# FLT04A.net
KiCad netlist of a schematic drawn in EAGLE
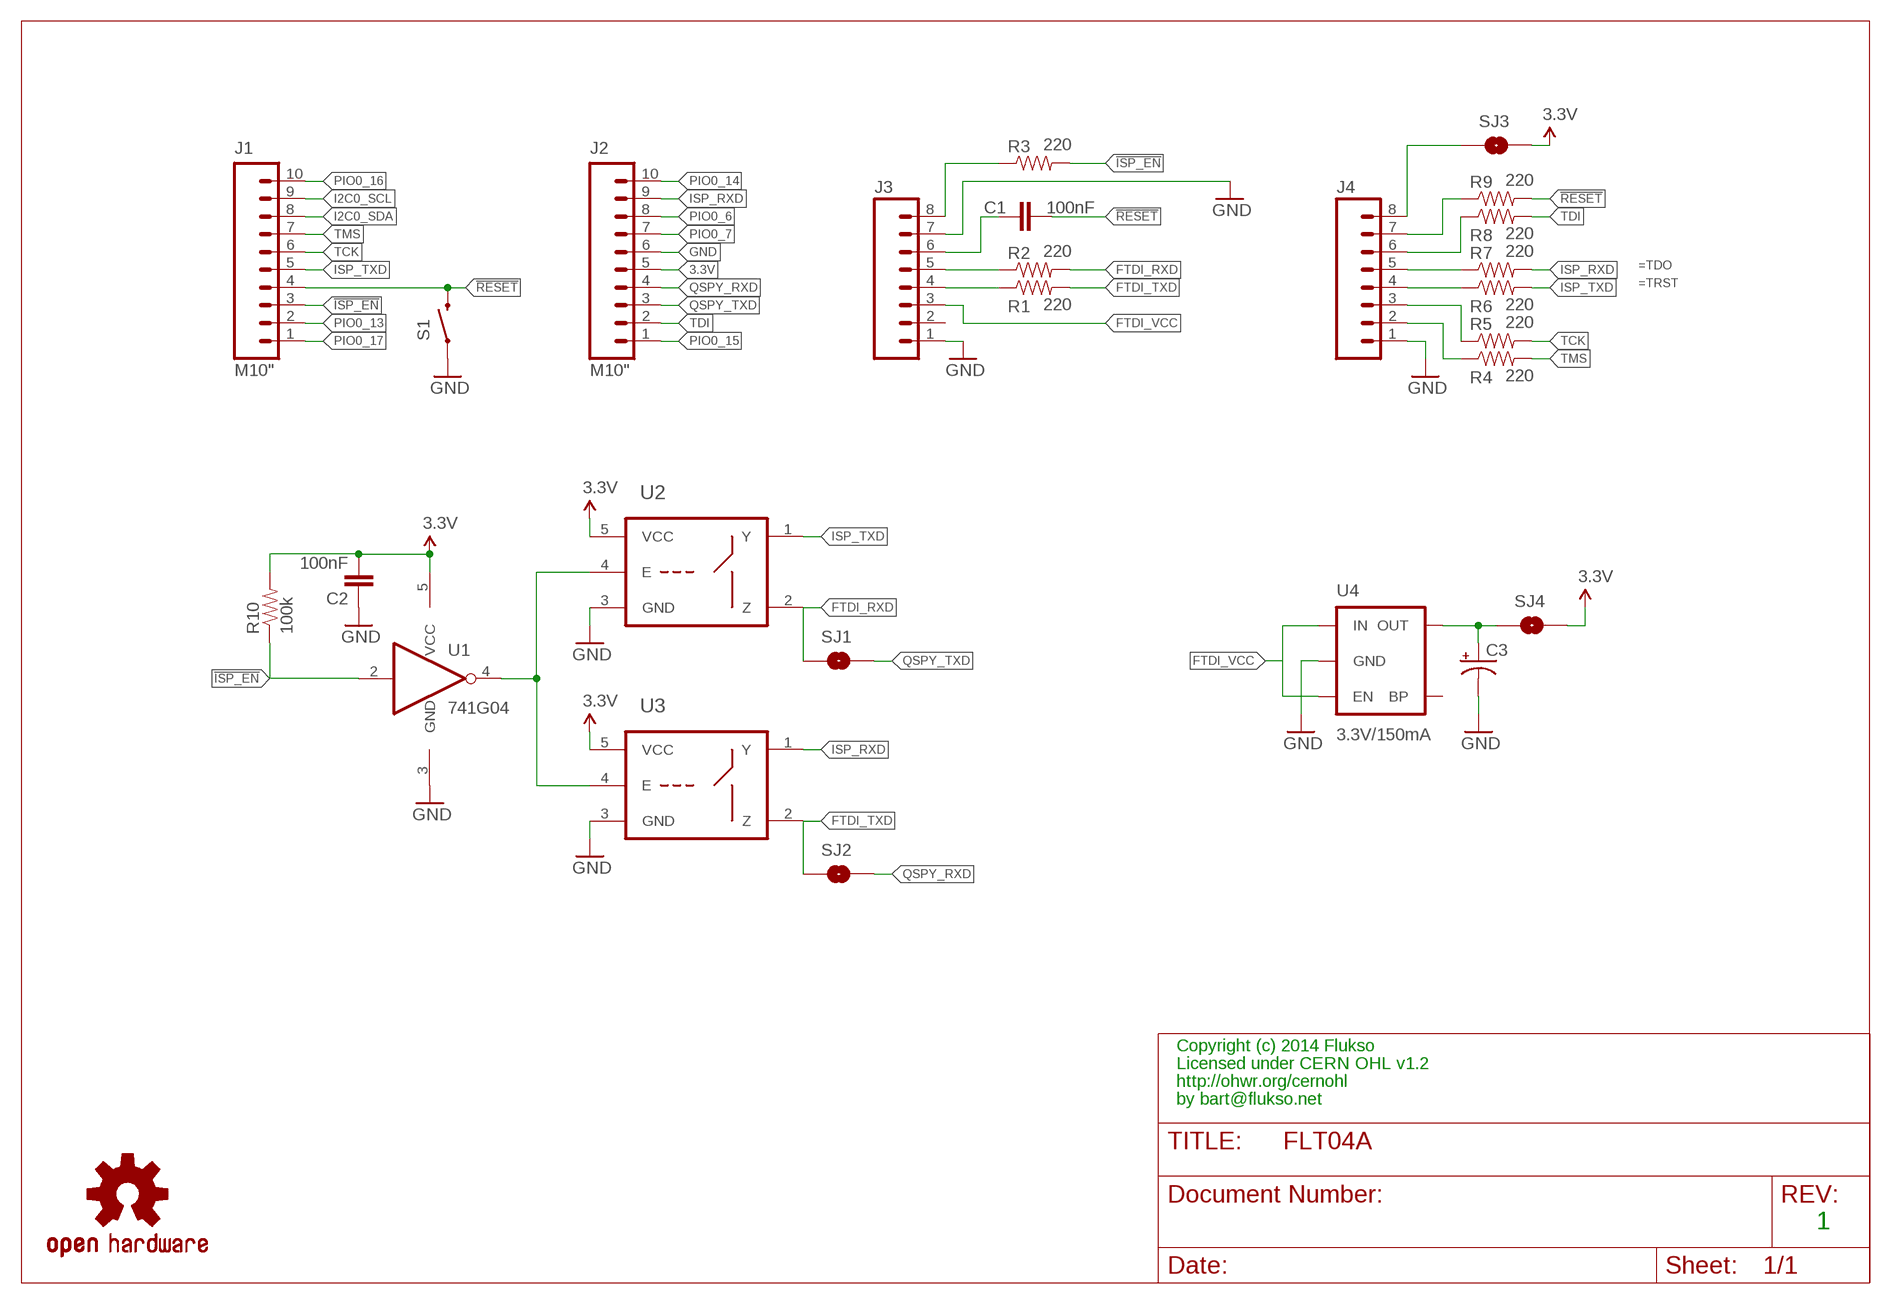
[diagram p0: schematic, sheet 1]

(export (version "E")
  (design (tool "Eeschema 10.0.6"))
  (components
    (comp (ref "C1")
      (value "100nF")
      (footprint "eagle-import:0402-CAP")
      (libsource (lib "eagle-import") (part "CAP0402-CAP"))
    )
    (comp (ref "C2")
      (value "100nF")
      (footprint "eagle-import:0402-CAP")
      (libsource (lib "eagle-import") (part "CAP0402-CAP"))
    )
    (comp (ref "C3")
      (value "CAP_POL1206")
      (footprint "eagle-import:EIA3216")
      (libsource (lib "eagle-import") (part "CAP_POL1206"))
    )
    (comp (ref "J1")
      (value "M10\"")
      (footprint "eagle-import:1X10")
      (libsource (lib "eagle-import") (part "M10{dblquote}"))
    )
    (comp (ref "J2")
      (value "M10\"")
      (footprint "eagle-import:1X10")
      (libsource (lib "eagle-import") (part "M10{dblquote}"))
    )
    (comp (ref "J3")
      (value "M08")
      (footprint "eagle-import:1X08_PIN1_NO_SILK")
      (libsource (lib "eagle-import") (part "M08"))
    )
    (comp (ref "J4")
      (value "M08")
      (footprint "eagle-import:1X08_PIN1_NO_SILK")
      (libsource (lib "eagle-import") (part "M08"))
    )
    (comp (ref "R1")
      (value "220")
      (footprint "eagle-import:0402-RES")
      (libsource (lib "eagle-import") (part "RESISTOR0402-RES"))
    )
    (comp (ref "R2")
      (value "220")
      (footprint "eagle-import:0402-RES")
      (libsource (lib "eagle-import") (part "RESISTOR0402-RES"))
    )
    (comp (ref "R3")
      (value "220")
      (footprint "eagle-import:0402-RES")
      (libsource (lib "eagle-import") (part "RESISTOR0402-RES"))
    )
    (comp (ref "R4")
      (value "220")
      (footprint "eagle-import:0402-RES")
      (libsource (lib "eagle-import") (part "RESISTOR0402-RES"))
    )
    (comp (ref "R5")
      (value "220")
      (footprint "eagle-import:0402-RES")
      (libsource (lib "eagle-import") (part "RESISTOR0402-RES"))
    )
    (comp (ref "R6")
      (value "220")
      (footprint "eagle-import:0402-RES")
      (libsource (lib "eagle-import") (part "RESISTOR0402-RES"))
    )
    (comp (ref "R7")
      (value "220")
      (footprint "eagle-import:0402-RES")
      (libsource (lib "eagle-import") (part "RESISTOR0402-RES"))
    )
    (comp (ref "R8")
      (value "220")
      (footprint "eagle-import:0402-RES")
      (libsource (lib "eagle-import") (part "RESISTOR0402-RES"))
    )
    (comp (ref "R9")
      (value "220")
      (footprint "eagle-import:0402-RES")
      (libsource (lib "eagle-import") (part "RESISTOR0402-RES"))
    )
    (comp (ref "R10")
      (value "100k")
      (footprint "eagle-import:0402-RES")
      (libsource (lib "eagle-import") (part "RESISTOR0402-RES"))
    )
    (comp (ref "S1")
      (value "SWITCH-MOMENTARY-2SMD")
      (footprint "eagle-import:TACTILE_SWITCH_SMD")
      (libsource (lib "eagle-import") (part "SWITCH-MOMENTARY-2SMD"))
    )
    (comp (ref "SJ1")
      (value "SOLDERJUMPERNC")
      (footprint "eagle-import:SJ_2S")
      (libsource (lib "eagle-import") (part "SOLDERJUMPERNC"))
    )
    (comp (ref "SJ2")
      (value "SOLDERJUMPERNC")
      (footprint "eagle-import:SJ_2S")
      (libsource (lib "eagle-import") (part "SOLDERJUMPERNC"))
    )
    (comp (ref "SJ3")
      (value "SOLDERJUMPERNC")
      (footprint "eagle-import:SJ_2S")
      (libsource (lib "eagle-import") (part "SOLDERJUMPERNC"))
    )
    (comp (ref "SJ4")
      (value "SOLDERJUMPERNC")
      (footprint "eagle-import:SJ_2S")
      (libsource (lib "eagle-import") (part "SOLDERJUMPERNC"))
    )
    (comp (ref "U$1")
      (value "OSHW-LOGOS")
      (footprint "eagle-import:OSHW-LOGO-S")
      (libsource (lib "eagle-import") (part "OSHW-LOGOS"))
    )
    (comp (ref "U1")
      (value "741G04")
      (footprint "eagle-import:SOT353")
      (libsource (lib "eagle-import") (part "741G04"))
    )
    (comp (ref "U2")
      (value "741G66")
      (footprint "eagle-import:SOT353")
      (libsource (lib "eagle-import") (part "741G66"))
    )
    (comp (ref "U3")
      (value "741G66")
      (footprint "eagle-import:SOT353")
      (libsource (lib "eagle-import") (part "741G66"))
    )
    (comp (ref "U4")
      (value "3.3V/150mA")
      (footprint "eagle-import:SOT23-5")
      (libsource (lib "eagle-import") (part "V_REG_MIC52053.3V"))
    )
  )
  (nets
    (net (code "1") (name "/~{ISP_EN}") (class "Default")
      (node (ref "J1") (pin "3") (pinfunction "3_3") (pintype "passive"))
      (node (ref "R10") (pin "1") (pinfunction "1_1") (pintype "passive"))
      (node (ref "R3") (pin "2") (pinfunction "2_2") (pintype "passive"))
      (node (ref "U1") (pin "2") (pinfunction "I_2") (pintype "input"))
    )
    (net (code "2") (name "/~{RESET}") (class "Default")
      (node (ref "C1") (pin "2") (pinfunction "2_2") (pintype "passive"))
      (node (ref "J1") (pin "4") (pinfunction "4_4") (pintype "passive"))
      (node (ref "R9") (pin "2") (pinfunction "2_2") (pintype "passive"))
      (node (ref "S1") (pin "3") (pinfunction "2_3") (pintype "passive"))
    )
    (net (code "3") (name "3.3V") (class "Default")
      (node (ref "C2") (pin "2") (pinfunction "2_2") (pintype "passive"))
      (node (ref "J2") (pin "5") (pinfunction "5_5") (pintype "passive"))
      (node (ref "R10") (pin "2") (pinfunction "2_2") (pintype "passive"))
      (node (ref "SJ3") (pin "2") (pinfunction "2_2") (pintype "passive"))
      (node (ref "SJ4") (pin "2") (pinfunction "2_2") (pintype "passive"))
      (node (ref "U1") (pin "5") (pinfunction "VCC_5") (pintype "power_in"))
      (node (ref "U2") (pin "5") (pinfunction "VCC_5") (pintype "power_in"))
      (node (ref "U3") (pin "5") (pinfunction "VCC_5") (pintype "power_in"))
    )
    (net (code "4") (name "FTDI_RXD") (class "Default")
      (node (ref "R2") (pin "2") (pinfunction "2_2") (pintype "passive"))
      (node (ref "SJ1") (pin "1") (pinfunction "1_1") (pintype "passive"))
      (node (ref "U2") (pin "2") (pinfunction "Z_2") (pintype "bidirectional"))
    )
    (net (code "5") (name "FTDI_TXD") (class "Default")
      (node (ref "R1") (pin "2") (pinfunction "2_2") (pintype "passive"))
      (node (ref "SJ2") (pin "1") (pinfunction "1_1") (pintype "passive"))
      (node (ref "U3") (pin "2") (pinfunction "Z_2") (pintype "bidirectional"))
    )
    (net (code "6") (name "FTDI_VCC") (class "Default")
      (node (ref "J3") (pin "3") (pinfunction "3_3") (pintype "passive"))
      (node (ref "U4") (pin "1") (pinfunction "IN_1") (pintype "input"))
      (node (ref "U4") (pin "3") (pinfunction "EN_3") (pintype "input"))
    )
    (net (code "7") (name "GND") (class "Default")
      (node (ref "C2") (pin "1") (pinfunction "1_1") (pintype "passive"))
      (node (ref "C3") (pin "C") (pinfunction "-_C") (pintype "passive"))
      (node (ref "J2") (pin "6") (pinfunction "6_6") (pintype "passive"))
      (node (ref "J3") (pin "1") (pinfunction "1_1") (pintype "passive"))
      (node (ref "J3") (pin "7") (pinfunction "7_7") (pintype "passive"))
      (node (ref "J4") (pin "1") (pinfunction "1_1") (pintype "passive"))
      (node (ref "S1") (pin "1") (pinfunction "1_1") (pintype "passive"))
      (node (ref "U1") (pin "3") (pinfunction "GND_3") (pintype "passive"))
      (node (ref "U2") (pin "3") (pinfunction "GND_3") (pintype "passive"))
      (node (ref "U3") (pin "3") (pinfunction "GND_3") (pintype "passive"))
      (node (ref "U4") (pin "2") (pinfunction "GND_2") (pintype "input"))
    )
    (net (code "8") (name "I2C0_SCL") (class "Default")
      (node (ref "J1") (pin "9") (pinfunction "9_9") (pintype "passive"))
    )
    (net (code "9") (name "I2C0_SDA") (class "Default")
      (node (ref "J1") (pin "8") (pinfunction "8_8") (pintype "passive"))
    )
    (net (code "10") (name "ISP_RXD") (class "Default")
      (node (ref "J2") (pin "9") (pinfunction "9_9") (pintype "passive"))
      (node (ref "R7") (pin "2") (pinfunction "2_2") (pintype "passive"))
      (node (ref "U3") (pin "1") (pinfunction "Y_1") (pintype "bidirectional"))
    )
    (net (code "11") (name "ISP_TXD") (class "Default")
      (node (ref "J1") (pin "5") (pinfunction "5_5") (pintype "passive"))
      (node (ref "R6") (pin "2") (pinfunction "2_2") (pintype "passive"))
      (node (ref "U2") (pin "1") (pinfunction "Y_1") (pintype "bidirectional"))
    )
    (net (code "12") (name "Net-(C1-Pad1)") (class "Default")
      (node (ref "C1") (pin "1") (pinfunction "1_1") (pintype "passive"))
      (node (ref "J3") (pin "6") (pinfunction "6_6") (pintype "passive"))
    )
    (net (code "13") (name "Net-(C3-+)") (class "Default")
      (node (ref "C3") (pin "A") (pinfunction "+_A") (pintype "passive"))
      (node (ref "SJ4") (pin "1") (pinfunction "1_1") (pintype "passive"))
      (node (ref "U4") (pin "5") (pinfunction "OUT_5") (pintype "passive"))
    )
    (net (code "14") (name "Net-(J3-Pad4)") (class "Default")
      (node (ref "J3") (pin "4") (pinfunction "4_4") (pintype "passive"))
      (node (ref "R1") (pin "1") (pinfunction "1_1") (pintype "passive"))
    )
    (net (code "15") (name "Net-(J3-Pad5)") (class "Default")
      (node (ref "J3") (pin "5") (pinfunction "5_5") (pintype "passive"))
      (node (ref "R2") (pin "1") (pinfunction "1_1") (pintype "passive"))
    )
    (net (code "16") (name "Net-(J3-Pad8)") (class "Default")
      (node (ref "J3") (pin "8") (pinfunction "8_8") (pintype "passive"))
      (node (ref "R3") (pin "1") (pinfunction "1_1") (pintype "passive"))
    )
    (net (code "17") (name "Net-(J4-Pad2)") (class "Default")
      (node (ref "J4") (pin "2") (pinfunction "2_2") (pintype "passive"))
      (node (ref "R4") (pin "1") (pinfunction "1_1") (pintype "passive"))
    )
    (net (code "18") (name "Net-(J4-Pad3)") (class "Default")
      (node (ref "J4") (pin "3") (pinfunction "3_3") (pintype "passive"))
      (node (ref "R5") (pin "1") (pinfunction "1_1") (pintype "passive"))
    )
    (net (code "19") (name "Net-(J4-Pad4)") (class "Default")
      (node (ref "J4") (pin "4") (pinfunction "4_4") (pintype "passive"))
      (node (ref "R6") (pin "1") (pinfunction "1_1") (pintype "passive"))
    )
    (net (code "20") (name "Net-(J4-Pad5)") (class "Default")
      (node (ref "J4") (pin "5") (pinfunction "5_5") (pintype "passive"))
      (node (ref "R7") (pin "1") (pinfunction "1_1") (pintype "passive"))
    )
    (net (code "21") (name "Net-(J4-Pad6)") (class "Default")
      (node (ref "J4") (pin "6") (pinfunction "6_6") (pintype "passive"))
      (node (ref "R8") (pin "1") (pinfunction "1_1") (pintype "passive"))
    )
    (net (code "22") (name "Net-(J4-Pad7)") (class "Default")
      (node (ref "J4") (pin "7") (pinfunction "7_7") (pintype "passive"))
      (node (ref "R9") (pin "1") (pinfunction "1_1") (pintype "passive"))
    )
    (net (code "23") (name "Net-(J4-Pad8)") (class "Default")
      (node (ref "J4") (pin "8") (pinfunction "8_8") (pintype "passive"))
      (node (ref "SJ3") (pin "1") (pinfunction "1_1") (pintype "passive"))
    )
    (net (code "24") (name "Net-(U1-O)") (class "Default")
      (node (ref "U1") (pin "4") (pinfunction "O_4") (pintype "output"))
      (node (ref "U2") (pin "4") (pinfunction "E_4") (pintype "input"))
      (node (ref "U3") (pin "4") (pinfunction "E_4") (pintype "input"))
    )
    (net (code "25") (name "PIO0_6") (class "Default")
      (node (ref "J2") (pin "8") (pinfunction "8_8") (pintype "passive"))
    )
    (net (code "26") (name "PIO0_7") (class "Default")
      (node (ref "J2") (pin "7") (pinfunction "7_7") (pintype "passive"))
    )
    (net (code "27") (name "PIO0_13") (class "Default")
      (node (ref "J1") (pin "2") (pinfunction "2_2") (pintype "passive"))
    )
    (net (code "28") (name "PIO0_14") (class "Default")
      (node (ref "J2") (pin "10") (pinfunction "10_10") (pintype "passive"))
    )
    (net (code "29") (name "PIO0_15") (class "Default")
      (node (ref "J2") (pin "1") (pinfunction "1_1") (pintype "passive"))
    )
    (net (code "30") (name "PIO0_16") (class "Default")
      (node (ref "J1") (pin "10") (pinfunction "10_10") (pintype "passive"))
    )
    (net (code "31") (name "PIO0_17") (class "Default")
      (node (ref "J1") (pin "1") (pinfunction "1_1") (pintype "passive"))
    )
    (net (code "32") (name "QSPY_RXD") (class "Default")
      (node (ref "J2") (pin "4") (pinfunction "4_4") (pintype "passive"))
      (node (ref "SJ2") (pin "2") (pinfunction "2_2") (pintype "passive"))
    )
    (net (code "33") (name "QSPY_TXD") (class "Default")
      (node (ref "J2") (pin "3") (pinfunction "3_3") (pintype "passive"))
      (node (ref "SJ1") (pin "2") (pinfunction "2_2") (pintype "passive"))
    )
    (net (code "34") (name "TCK") (class "Default")
      (node (ref "J1") (pin "6") (pinfunction "6_6") (pintype "passive"))
      (node (ref "R5") (pin "2") (pinfunction "2_2") (pintype "passive"))
    )
    (net (code "35") (name "TDI") (class "Default")
      (node (ref "J2") (pin "2") (pinfunction "2_2") (pintype "passive"))
      (node (ref "R8") (pin "2") (pinfunction "2_2") (pintype "passive"))
    )
    (net (code "36") (name "TMS") (class "Default")
      (node (ref "J1") (pin "7") (pinfunction "7_7") (pintype "passive"))
      (node (ref "R4") (pin "2") (pinfunction "2_2") (pintype "passive"))
    )
    (net (code "37") (name "unconnected-(J3-Pad2)") (class "Default")
      (node (ref "J3") (pin "2") (pinfunction "2_2") (pintype "passive"))
    )
    (net (code "38") (name "unconnected-(U4-BP-Pad4)") (class "Default")
      (node (ref "U4") (pin "4") (pinfunction "BP_4") (pintype "input"))
    )
  )
)
